# schematic.net
KiCad netlist of a schematic drawn in EasyEDA
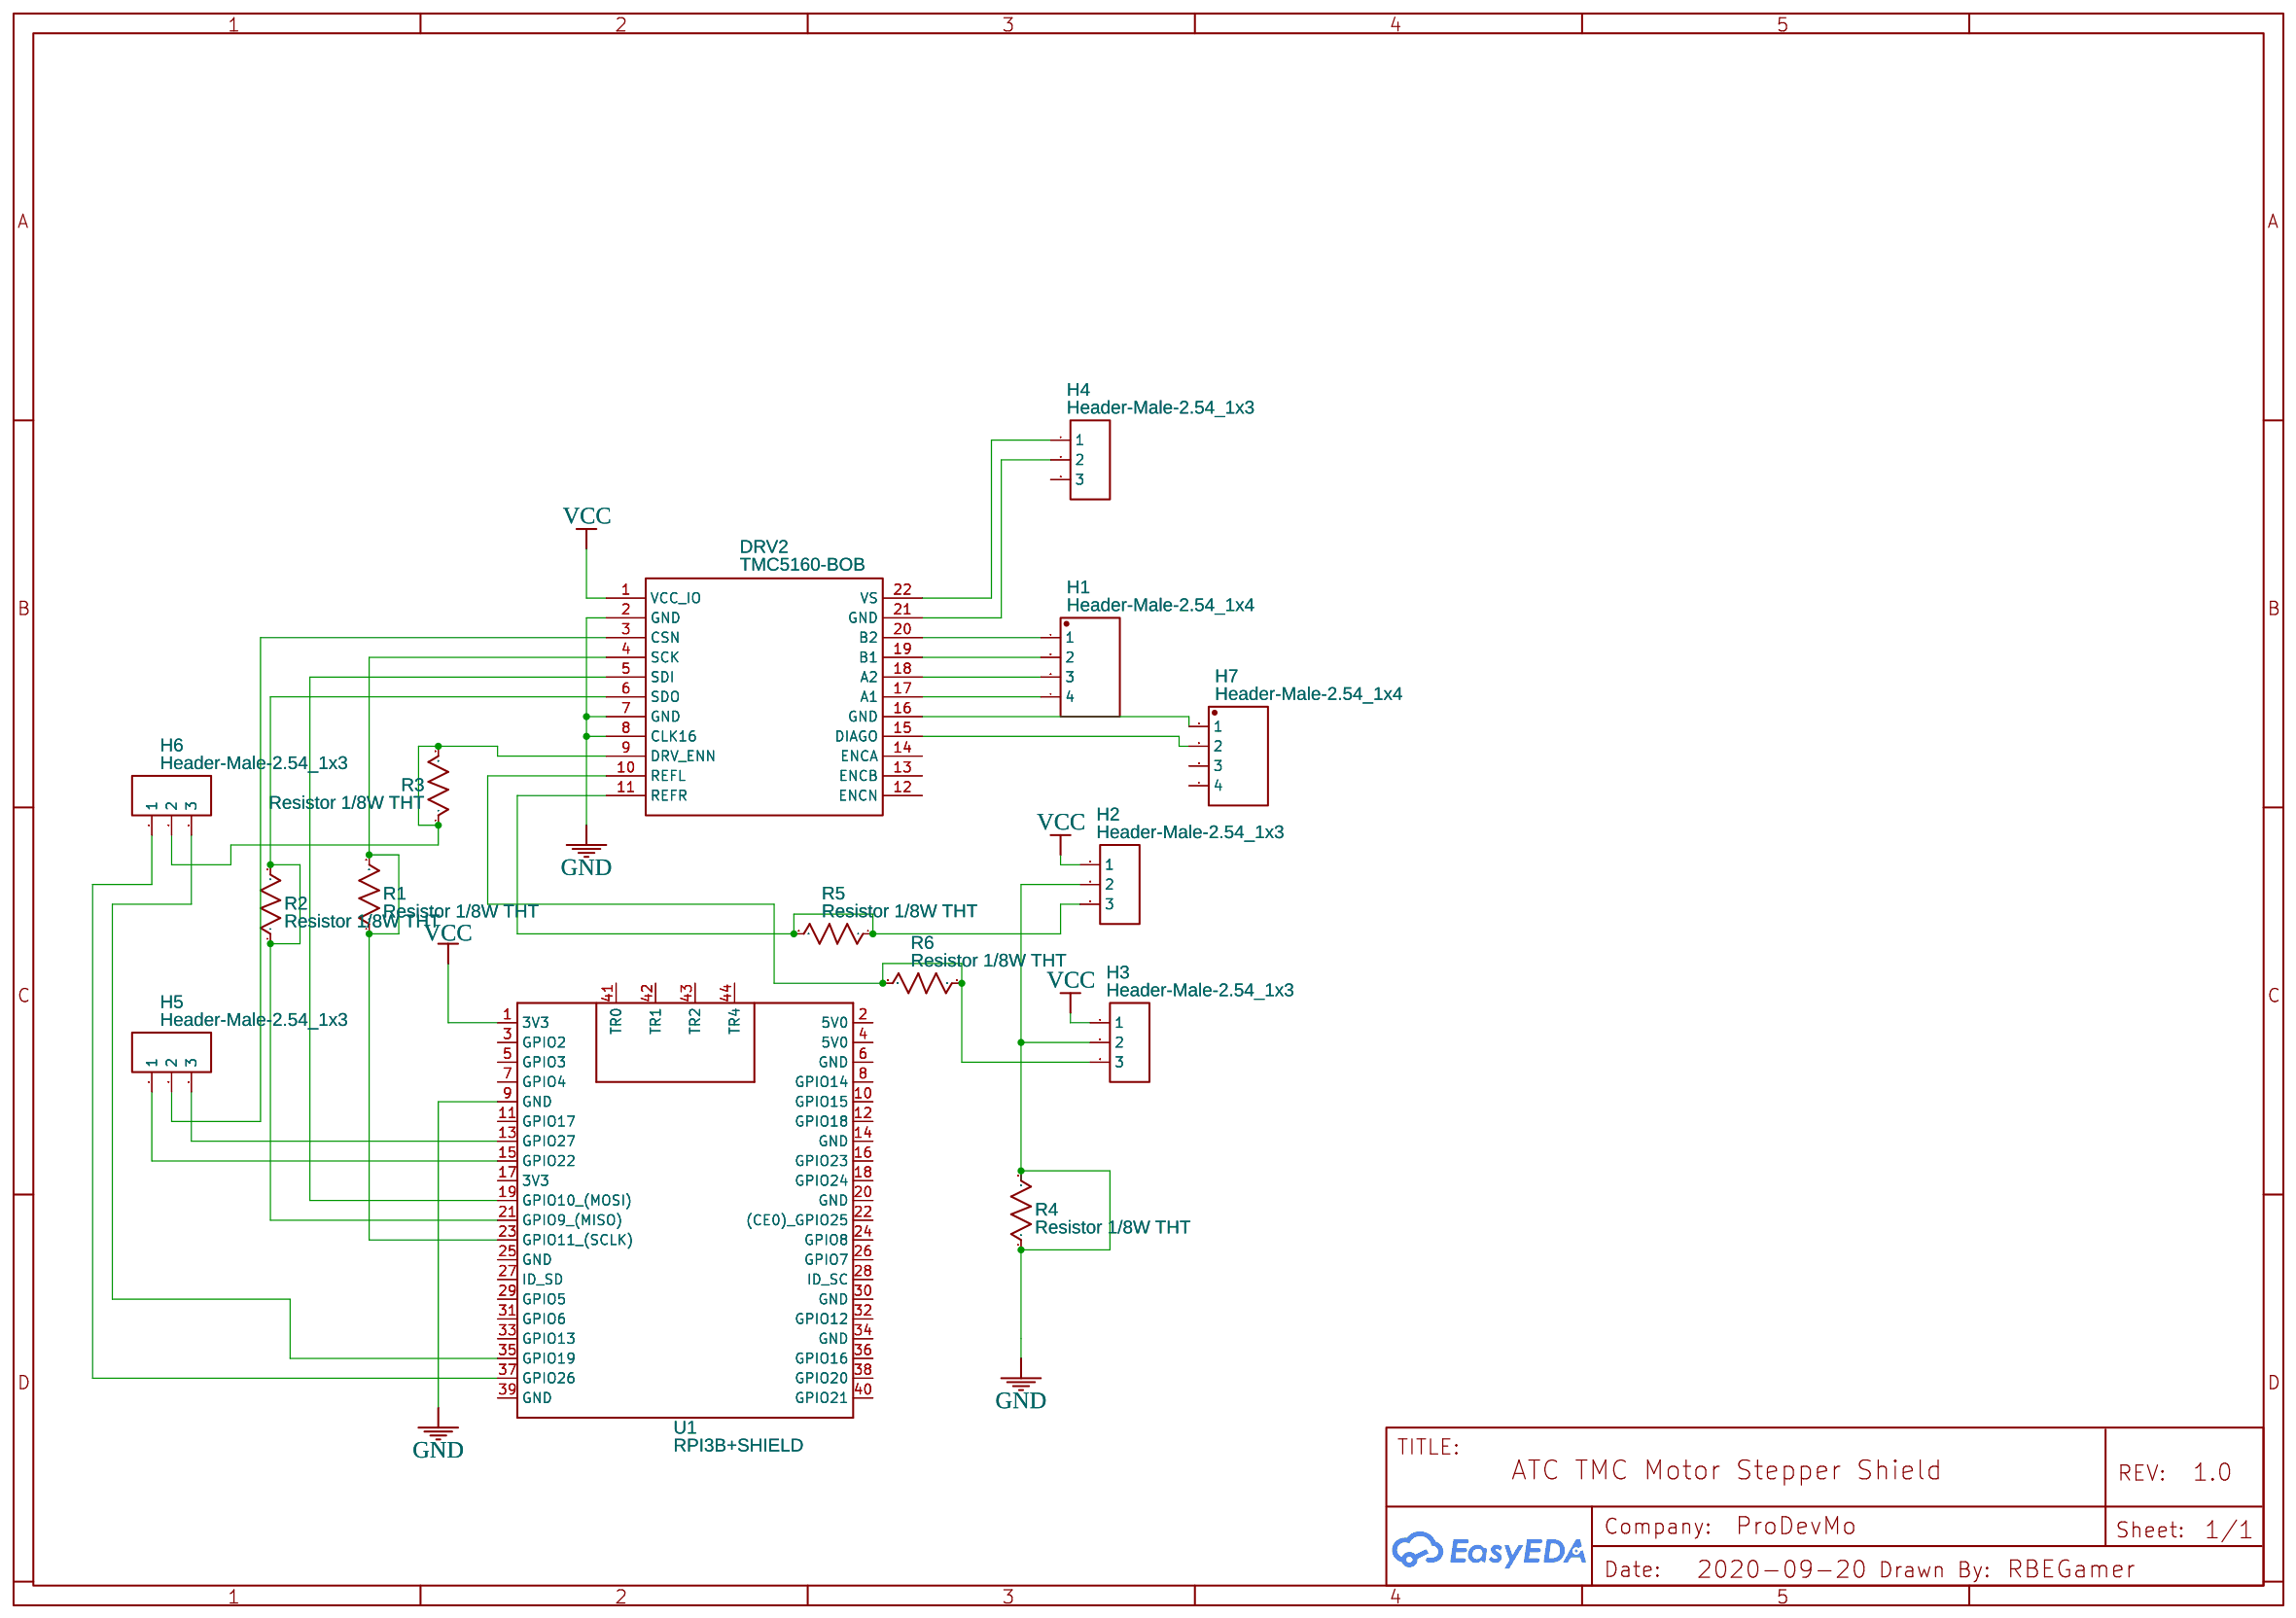
[diagram p0: schematic sheet]

(export (version "E")
  (design (tool "Eeschema 10.0.6"))
  (components
    (comp (ref "DRV2") (value "TMC5160-BOB") (libsource (lib "") (part "TMC5160-BOB")))
    (comp (ref "H1")
      (value "Header-Male-2.54_1x4")
      (fields
        (field (name "BOM_Manufacturer Part") "210S-1*4P L=11.6MMGold-plated black")
        (field (name "BOM_Supplier Part") "C124378")
      )
      (libsource (lib "") (part "Header-Male-2.54_1x4"))
    )
    (comp (ref "H2")
      (value "Header-Male-2.54_1x3")
      (fields
        (field (name "BOM_Manufacturer Part") "Header2.54mm 1*3P")
        (field (name "BOM_Supplier Part") "C49257")
      )
      (libsource (lib "") (part "Header-Male-2.54_1x3_1"))
    )
    (comp (ref "H3")
      (value "Header-Male-2.54_1x3")
      (fields
        (field (name "BOM_Manufacturer Part") "Header2.54mm 1*3P")
        (field (name "BOM_Supplier Part") "C49257")
      )
      (libsource (lib "") (part "Header-Male-2.54_1x3_1"))
    )
    (comp (ref "H4")
      (value "Header-Male-2.54_1x3")
      (fields
        (field (name "BOM_Manufacturer Part") "Header2.54mm 1*3P")
        (field (name "BOM_Supplier Part") "C49257")
      )
      (libsource (lib "") (part "Header-Male-2.54_1x3_1"))
    )
    (comp (ref "H5")
      (value "Header-Male-2.54_1x3")
      (fields
        (field (name "BOM_Manufacturer Part") "Header2.54mm 1*3P")
        (field (name "BOM_Supplier Part") "C49257")
      )
      (libsource (lib "") (part "Header-Male-2.54_1x3"))
    )
    (comp (ref "H6")
      (value "Header-Male-2.54_1x3")
      (fields
        (field (name "BOM_Manufacturer Part") "Header2.54mm 1*3P")
        (field (name "BOM_Supplier Part") "C49257")
      )
      (libsource (lib "") (part "Header-Male-2.54_1x3"))
    )
    (comp (ref "H7")
      (value "Header-Male-2.54_1x4")
      (fields
        (field (name "BOM_Manufacturer Part") "210S-1*4P L=11.6MMGold-plated black")
        (field (name "BOM_Supplier Part") "C124378")
      )
      (libsource (lib "") (part "Header-Male-2.54_1x4"))
    )
    (comp (ref "R1")
      (value "Resistor 1/8W THT")
      (fields (field (name "BOM_Manufacturer Part") "Generic"))
      (libsource (lib "") (part "Resistor 1/8W THT"))
    )
    (comp (ref "R2")
      (value "Resistor 1/8W THT")
      (fields (field (name "BOM_Manufacturer Part") "Generic"))
      (libsource (lib "") (part "Resistor 1/8W THT"))
    )
    (comp (ref "R3")
      (value "Resistor 1/8W THT")
      (fields (field (name "BOM_Manufacturer Part") "Generic"))
      (libsource (lib "") (part "Resistor 1/8W THT_2"))
    )
    (comp (ref "R4")
      (value "Resistor 1/8W THT")
      (fields (field (name "BOM_Manufacturer Part") "Generic"))
      (libsource (lib "") (part "Resistor 1/8W THT"))
    )
    (comp (ref "R5")
      (value "Resistor 1/8W THT")
      (fields (field (name "BOM_Manufacturer Part") "Generic"))
      (libsource (lib "") (part "Resistor 1/8W THT_1"))
    )
    (comp (ref "R6")
      (value "Resistor 1/8W THT")
      (fields (field (name "BOM_Manufacturer Part") "Generic"))
      (libsource (lib "") (part "Resistor 1/8W THT_1"))
    )
    (comp (ref "U1")
      (value "RPI3B+SHIELD")
      (fields (field (name "BOM_Manufacturer Part") "RaspberryPi 3"))
      (libsource (lib "") (part "RPI3B+SHIELD"))
    )
  )
  (nets
    (net (code "1") (name "GND") (class "Default")
      (node (ref "DRV2") (pin "2") (pinfunction "GND_2") (pintype "unspecified"))
      (node (ref "DRV2") (pin "7") (pinfunction "GND_7") (pintype "unspecified"))
      (node (ref "DRV2") (pin "8") (pinfunction "CLK16_8") (pintype "unspecified"))
      (node (ref "H2") (pin "2") (pinfunction "2_2") (pintype "input"))
      (node (ref "H3") (pin "2") (pinfunction "2_2") (pintype "input"))
      (node (ref "R4") (pin "1") (pinfunction "1_1") (pintype "unspecified"))
      (node (ref "R4") (pin "2") (pinfunction "2_2") (pintype "unspecified"))
      (node (ref "U1") (pin "9") (pinfunction "GND_9") (pintype "unspecified"))
    )
    (net (code "2") (name "Net-(DRV2-A1)") (class "Default")
      (node (ref "DRV2") (pin "17") (pinfunction "A1_17") (pintype "unspecified"))
      (node (ref "H1") (pin "4") (pinfunction "4_4") (pintype "unspecified"))
    )
    (net (code "3") (name "Net-(DRV2-A2)") (class "Default")
      (node (ref "DRV2") (pin "18") (pinfunction "A2_18") (pintype "unspecified"))
      (node (ref "H1") (pin "3") (pinfunction "3_3") (pintype "unspecified"))
    )
    (net (code "4") (name "Net-(DRV2-B1)") (class "Default")
      (node (ref "DRV2") (pin "19") (pinfunction "B1_19") (pintype "unspecified"))
      (node (ref "H1") (pin "2") (pinfunction "2_2") (pintype "unspecified"))
    )
    (net (code "5") (name "Net-(DRV2-B2)") (class "Default")
      (node (ref "DRV2") (pin "20") (pinfunction "B2_20") (pintype "unspecified"))
      (node (ref "H1") (pin "1") (pinfunction "1_1") (pintype "unspecified"))
    )
    (net (code "6") (name "Net-(DRV2-CSN)") (class "Default")
      (node (ref "DRV2") (pin "3") (pinfunction "CSN_3") (pintype "unspecified"))
      (node (ref "H5") (pin "2") (pinfunction "2_2") (pintype "input"))
    )
    (net (code "7") (name "Net-(DRV2-DIAGO)") (class "Default")
      (node (ref "DRV2") (pin "15") (pinfunction "DIAGO_15") (pintype "unspecified"))
      (node (ref "H7") (pin "2") (pinfunction "2_2") (pintype "unspecified"))
    )
    (net (code "8") (name "Net-(DRV2-DRV_ENN)") (class "Default")
      (node (ref "DRV2") (pin "9") (pinfunction "DRV_ENN_9") (pintype "unspecified"))
      (node (ref "H6") (pin "2") (pinfunction "2_2") (pintype "input"))
      (node (ref "R3") (pin "1") (pinfunction "1_1") (pintype "unspecified"))
      (node (ref "R3") (pin "2") (pinfunction "2_2") (pintype "unspecified"))
    )
    (net (code "9") (name "Net-(DRV2-GND-Pad16)") (class "Default")
      (node (ref "DRV2") (pin "16") (pinfunction "GND_16") (pintype "unspecified"))
      (node (ref "H7") (pin "1") (pinfunction "1_1") (pintype "unspecified"))
    )
    (net (code "10") (name "Net-(DRV2-GND-Pad21)") (class "Default")
      (node (ref "DRV2") (pin "21") (pinfunction "GND_21") (pintype "unspecified"))
      (node (ref "H4") (pin "2") (pinfunction "2_2") (pintype "input"))
    )
    (net (code "11") (name "Net-(DRV2-REFL)") (class "Default")
      (node (ref "DRV2") (pin "10") (pinfunction "REFL_10") (pintype "unspecified"))
      (node (ref "H3") (pin "3") (pinfunction "3_3") (pintype "input"))
      (node (ref "R6") (pin "1") (pinfunction "1_1") (pintype "unspecified"))
      (node (ref "R6") (pin "2") (pinfunction "2_2") (pintype "unspecified"))
    )
    (net (code "12") (name "Net-(DRV2-REFR)") (class "Default")
      (node (ref "DRV2") (pin "11") (pinfunction "REFR_11") (pintype "unspecified"))
      (node (ref "H2") (pin "3") (pinfunction "3_3") (pintype "input"))
      (node (ref "R5") (pin "1") (pinfunction "1_1") (pintype "unspecified"))
      (node (ref "R5") (pin "2") (pinfunction "2_2") (pintype "unspecified"))
    )
    (net (code "13") (name "Net-(DRV2-SCK)") (class "Default")
      (node (ref "DRV2") (pin "4") (pinfunction "SCK_4") (pintype "unspecified"))
      (node (ref "R1") (pin "1") (pinfunction "1_1") (pintype "unspecified"))
      (node (ref "R1") (pin "2") (pinfunction "2_2") (pintype "unspecified"))
      (node (ref "U1") (pin "23") (pinfunction "GPIO11_(SCLK)_23") (pintype "unspecified"))
    )
    (net (code "14") (name "Net-(DRV2-SDI)") (class "Default")
      (node (ref "DRV2") (pin "5") (pinfunction "SDI_5") (pintype "unspecified"))
      (node (ref "U1") (pin "19") (pinfunction "GPIO10_(MOSI)_19") (pintype "unspecified"))
    )
    (net (code "15") (name "Net-(DRV2-SDO)") (class "Default")
      (node (ref "DRV2") (pin "6") (pinfunction "SDO_6") (pintype "unspecified"))
      (node (ref "R2") (pin "1") (pinfunction "1_1") (pintype "unspecified"))
      (node (ref "R2") (pin "2") (pinfunction "2_2") (pintype "unspecified"))
      (node (ref "U1") (pin "21") (pinfunction "GPIO9_(MISO)_21") (pintype "unspecified"))
    )
    (net (code "16") (name "Net-(DRV2-VS)") (class "Default")
      (node (ref "DRV2") (pin "22") (pinfunction "VS_22") (pintype "unspecified"))
      (node (ref "H4") (pin "1") (pinfunction "1_1") (pintype "input"))
    )
    (net (code "17") (name "Net-(U1-GPIO19)") (class "Default")
      (node (ref "H6") (pin "3") (pinfunction "3_3") (pintype "input"))
      (node (ref "U1") (pin "35") (pinfunction "GPIO19_35") (pintype "unspecified"))
    )
    (net (code "18") (name "Net-(U1-GPIO22)") (class "Default")
      (node (ref "H5") (pin "1") (pinfunction "1_1") (pintype "input"))
      (node (ref "U1") (pin "15") (pinfunction "GPIO22_15") (pintype "unspecified"))
    )
    (net (code "19") (name "Net-(U1-GPIO26)") (class "Default")
      (node (ref "H6") (pin "1") (pinfunction "1_1") (pintype "input"))
      (node (ref "U1") (pin "37") (pinfunction "GPIO26_37") (pintype "unspecified"))
    )
    (net (code "20") (name "Net-(U1-GPIO27)") (class "Default")
      (node (ref "H5") (pin "3") (pinfunction "3_3") (pintype "input"))
      (node (ref "U1") (pin "13") (pinfunction "GPIO27_13") (pintype "unspecified"))
    )
    (net (code "21") (name "VCC") (class "Default")
      (node (ref "DRV2") (pin "1") (pinfunction "VCC_IO_1") (pintype "unspecified"))
      (node (ref "H2") (pin "1") (pinfunction "1_1") (pintype "input"))
      (node (ref "H3") (pin "1") (pinfunction "1_1") (pintype "input"))
      (node (ref "U1") (pin "1") (pinfunction "3V3_1") (pintype "unspecified"))
    )
    (net (code "22") (name "unconnected-(DRV2-ENCA-Pad14)") (class "Default")
      (node (ref "DRV2") (pin "14") (pinfunction "ENCA_14") (pintype "unspecified"))
    )
    (net (code "23") (name "unconnected-(DRV2-ENCB-Pad13)") (class "Default")
      (node (ref "DRV2") (pin "13") (pinfunction "ENCB_13") (pintype "unspecified"))
    )
    (net (code "24") (name "unconnected-(DRV2-ENCN-Pad12)") (class "Default")
      (node (ref "DRV2") (pin "12") (pinfunction "ENCN_12") (pintype "unspecified"))
    )
    (net (code "25") (name "unconnected-(H4-Pad3)") (class "Default")
      (node (ref "H4") (pin "3") (pinfunction "3_3") (pintype "input"))
    )
    (net (code "26") (name "unconnected-(H7-Pad3)") (class "Default")
      (node (ref "H7") (pin "3") (pinfunction "3_3") (pintype "unspecified"))
    )
    (net (code "27") (name "unconnected-(H7-Pad4)") (class "Default")
      (node (ref "H7") (pin "4") (pinfunction "4_4") (pintype "unspecified"))
    )
    (net (code "28") (name "unconnected-(U1-(CE0)_GPIO25-Pad22)") (class "Default")
      (node (ref "U1") (pin "22") (pinfunction "(CE0)_GPIO25_22") (pintype "unspecified"))
    )
    (net (code "29") (name "unconnected-(U1-3V3-Pad17)") (class "Default")
      (node (ref "U1") (pin "17") (pinfunction "3V3_17") (pintype "unspecified"))
    )
    (net (code "30") (name "unconnected-(U1-5V0-Pad2)") (class "Default")
      (node (ref "U1") (pin "2") (pinfunction "5V0_2") (pintype "unspecified"))
    )
    (net (code "31") (name "unconnected-(U1-5V0-Pad4)") (class "Default")
      (node (ref "U1") (pin "4") (pinfunction "5V0_4") (pintype "unspecified"))
    )
    (net (code "32") (name "unconnected-(U1-GND-Pad6)") (class "Default")
      (node (ref "U1") (pin "6") (pinfunction "GND_6") (pintype "unspecified"))
    )
    (net (code "33") (name "unconnected-(U1-GND-Pad14)") (class "Default")
      (node (ref "U1") (pin "14") (pinfunction "GND_14") (pintype "unspecified"))
    )
    (net (code "34") (name "unconnected-(U1-GND-Pad20)") (class "Default")
      (node (ref "U1") (pin "20") (pinfunction "GND_20") (pintype "unspecified"))
    )
    (net (code "35") (name "unconnected-(U1-GND-Pad25)") (class "Default")
      (node (ref "U1") (pin "25") (pinfunction "GND_25") (pintype "unspecified"))
    )
    (net (code "36") (name "unconnected-(U1-GND-Pad30)") (class "Default")
      (node (ref "U1") (pin "30") (pinfunction "GND_30") (pintype "unspecified"))
    )
    (net (code "37") (name "unconnected-(U1-GND-Pad34)") (class "Default")
      (node (ref "U1") (pin "34") (pinfunction "GND_34") (pintype "unspecified"))
    )
    (net (code "38") (name "unconnected-(U1-GND-Pad39)") (class "Default")
      (node (ref "U1") (pin "39") (pinfunction "GND_39") (pintype "unspecified"))
    )
    (net (code "39") (name "unconnected-(U1-GPIO2-Pad3)") (class "Default")
      (node (ref "U1") (pin "3") (pinfunction "GPIO2_3") (pintype "unspecified"))
    )
    (net (code "40") (name "unconnected-(U1-GPIO3-Pad5)") (class "Default")
      (node (ref "U1") (pin "5") (pinfunction "GPIO3_5") (pintype "unspecified"))
    )
    (net (code "41") (name "unconnected-(U1-GPIO4-Pad7)") (class "Default")
      (node (ref "U1") (pin "7") (pinfunction "GPIO4_7") (pintype "unspecified"))
    )
    (net (code "42") (name "unconnected-(U1-GPIO5-Pad29)") (class "Default")
      (node (ref "U1") (pin "29") (pinfunction "GPIO5_29") (pintype "unspecified"))
    )
    (net (code "43") (name "unconnected-(U1-GPIO6-Pad31)") (class "Default")
      (node (ref "U1") (pin "31") (pinfunction "GPIO6_31") (pintype "unspecified"))
    )
    (net (code "44") (name "unconnected-(U1-GPIO7-Pad26)") (class "Default")
      (node (ref "U1") (pin "26") (pinfunction "GPIO7_26") (pintype "unspecified"))
    )
    (net (code "45") (name "unconnected-(U1-GPIO8-Pad24)") (class "Default")
      (node (ref "U1") (pin "24") (pinfunction "GPIO8_24") (pintype "unspecified"))
    )
    (net (code "46") (name "unconnected-(U1-GPIO12-Pad32)") (class "Default")
      (node (ref "U1") (pin "32") (pinfunction "GPIO12_32") (pintype "unspecified"))
    )
    (net (code "47") (name "unconnected-(U1-GPIO13-Pad33)") (class "Default")
      (node (ref "U1") (pin "33") (pinfunction "GPIO13_33") (pintype "unspecified"))
    )
    (net (code "48") (name "unconnected-(U1-GPIO14-Pad8)") (class "Default")
      (node (ref "U1") (pin "8") (pinfunction "GPIO14_8") (pintype "unspecified"))
    )
    (net (code "49") (name "unconnected-(U1-GPIO15-Pad10)") (class "Default")
      (node (ref "U1") (pin "10") (pinfunction "GPIO15_10") (pintype "unspecified"))
    )
    (net (code "50") (name "unconnected-(U1-GPIO16-Pad36)") (class "Default")
      (node (ref "U1") (pin "36") (pinfunction "GPIO16_36") (pintype "unspecified"))
    )
    (net (code "51") (name "unconnected-(U1-GPIO17-Pad11)") (class "Default")
      (node (ref "U1") (pin "11") (pinfunction "GPIO17_11") (pintype "unspecified"))
    )
    (net (code "52") (name "unconnected-(U1-GPIO18-Pad12)") (class "Default")
      (node (ref "U1") (pin "12") (pinfunction "GPIO18_12") (pintype "unspecified"))
    )
    (net (code "53") (name "unconnected-(U1-GPIO20-Pad38)") (class "Default")
      (node (ref "U1") (pin "38") (pinfunction "GPIO20_38") (pintype "unspecified"))
    )
    (net (code "54") (name "unconnected-(U1-GPIO21-Pad40)") (class "Default")
      (node (ref "U1") (pin "40") (pinfunction "GPIO21_40") (pintype "unspecified"))
    )
    (net (code "55") (name "unconnected-(U1-GPIO23-Pad16)") (class "Default")
      (node (ref "U1") (pin "16") (pinfunction "GPIO23_16") (pintype "unspecified"))
    )
    (net (code "56") (name "unconnected-(U1-GPIO24-Pad18)") (class "Default")
      (node (ref "U1") (pin "18") (pinfunction "GPIO24_18") (pintype "unspecified"))
    )
    (net (code "57") (name "unconnected-(U1-ID_SC-Pad28)") (class "Default")
      (node (ref "U1") (pin "28") (pinfunction "ID_SC_28") (pintype "unspecified"))
    )
    (net (code "58") (name "unconnected-(U1-ID_SD-Pad27)") (class "Default")
      (node (ref "U1") (pin "27") (pinfunction "ID_SD_27") (pintype "unspecified"))
    )
    (net (code "59") (name "unconnected-(U1-TR0-Pad41)") (class "Default")
      (node (ref "U1") (pin "41") (pinfunction "TR0_41") (pintype "unspecified"))
    )
    (net (code "60") (name "unconnected-(U1-TR1-Pad42)") (class "Default")
      (node (ref "U1") (pin "42") (pinfunction "TR1_42") (pintype "unspecified"))
    )
    (net (code "61") (name "unconnected-(U1-TR2-Pad43)") (class "Default")
      (node (ref "U1") (pin "43") (pinfunction "TR2_43") (pintype "unspecified"))
    )
    (net (code "62") (name "unconnected-(U1-TR4-Pad44)") (class "Default")
      (node (ref "U1") (pin "44") (pinfunction "TR4_44") (pintype "unspecified"))
    )
  )
)
